# 23005_4.net
KiCad netlist of a schematic drawn in Altium Designer
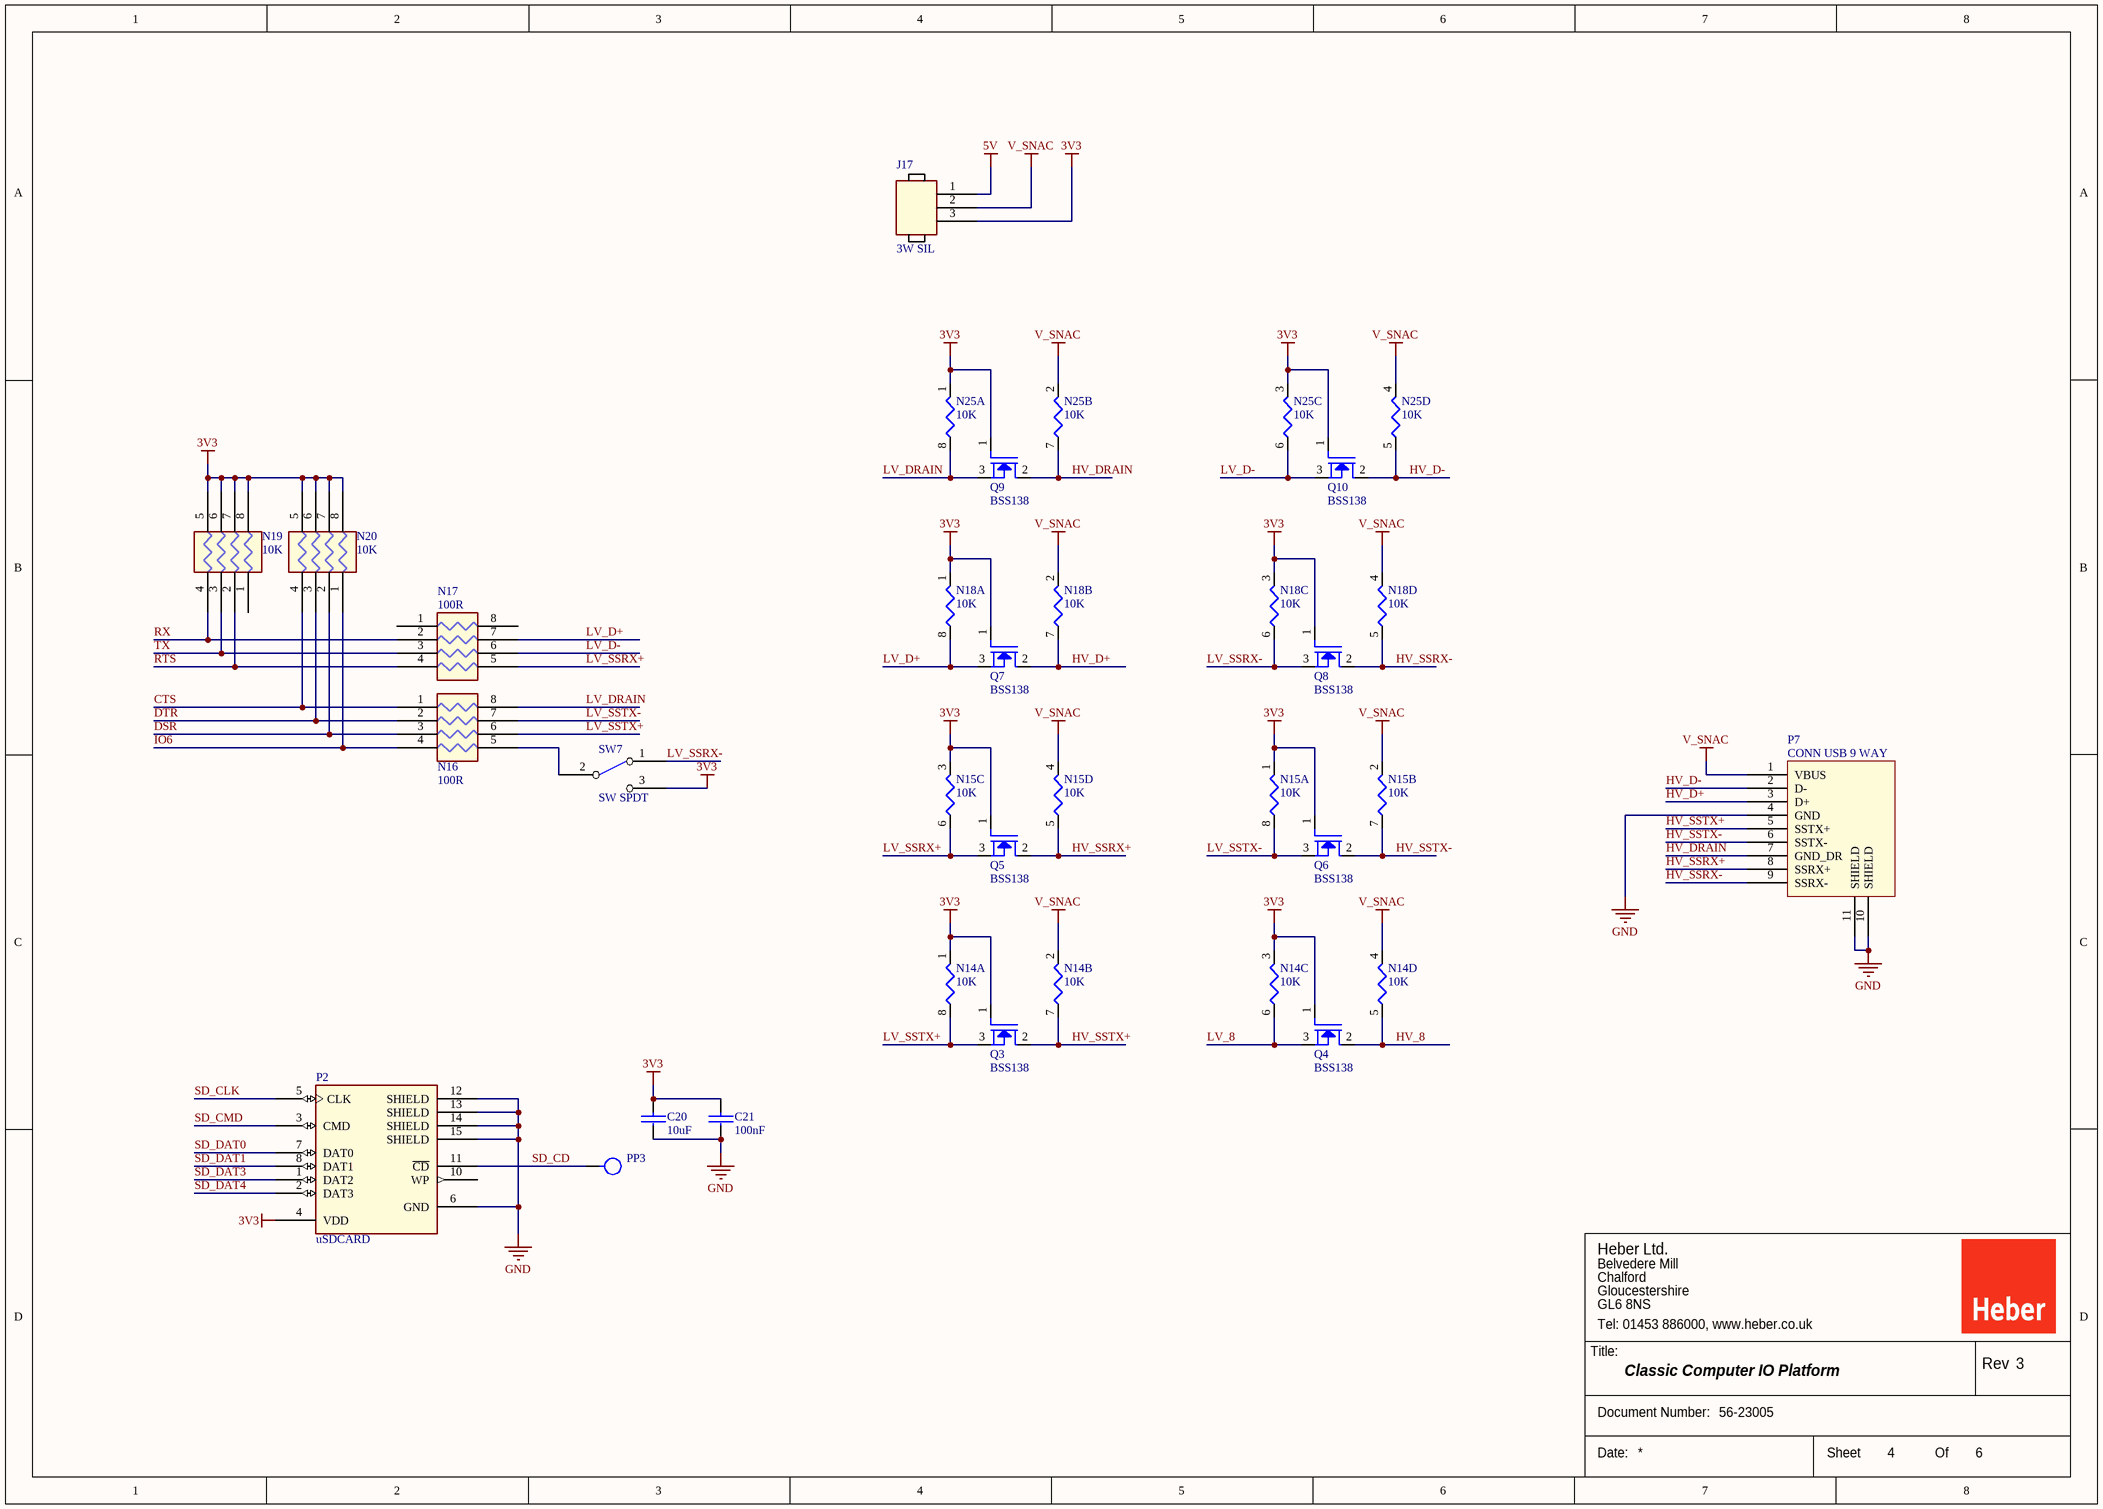
[diagram p0: 23005_4.SchDoc]

(export (version "E")
  (design (tool "Eeschema 10.0.6"))
  (components
    (comp (ref "C20") (value "10uF") (footprint "SM0805") (libsource (lib "LIBRARY1_Library") (part "C")))
    (comp (ref "C21") (value "100nF") (footprint "SM0603") (libsource (lib "LIBRARY1_Library") (part "C")))
    (comp (ref "J17")
      (value "3W SIL")
      (footprint "3WSIL")
      (libsource (lib "LIBRARY1_Library") (part "HEADER 3"))
    )
    (comp (ref "N14")
      (value "10K")
      (footprint "1206RES4_I2")
      (libsource (lib "LIBRARY1_Library") (part "RESISTOR DIP 4 A-D"))
    )
    (comp (ref "N15")
      (value "10K")
      (footprint "1206RES4_I2")
      (libsource (lib "LIBRARY1_Library") (part "RESISTOR DIP 4 A-D"))
    )
    (comp (ref "N16")
      (value "100R")
      (footprint "1206RES4_I2")
      (libsource (lib "LIBRARY1_Library") (part "RESISTOR DIP 4"))
    )
    (comp (ref "N17")
      (value "100R")
      (footprint "1206RES4_I2")
      (libsource (lib "LIBRARY1_Library") (part "RESISTOR DIP 4"))
    )
    (comp (ref "N18")
      (value "10K")
      (footprint "1206RES4_I2")
      (libsource (lib "LIBRARY1_Library") (part "RESISTOR DIP 4 A-D"))
    )
    (comp (ref "N19")
      (value "10K")
      (footprint "1206RES4_I2")
      (libsource (lib "LIBRARY1_Library") (part "RESISTOR DIP 4"))
    )
    (comp (ref "N20")
      (value "10K")
      (footprint "1206RES4_I2")
      (libsource (lib "LIBRARY1_Library") (part "RESISTOR DIP 4"))
    )
    (comp (ref "N25")
      (value "10K")
      (footprint "1206RES4_I2")
      (libsource (lib "LIBRARY1_Library") (part "RESISTOR DIP 4 A-D"))
    )
    (comp (ref "P2")
      (value "uSDCARD")
      (footprint "AMP_114-00841-68")
      (libsource (lib "LIBRARY1_Library") (part "uSDCARD"))
    )
    (comp (ref "P7")
      (value "CONN USB 9 WAY")
      (footprint "WURTH_692121030100")
      (libsource (lib "23005") (part "CONN USB 9 WAY"))
    )
    (comp (ref "PP3")
      (value "PROBEPOINT_SHORT")
      (footprint "PROBEPOINT")
      (libsource (lib "LIBRARY1_Library") (part "PROBEPOINT_SHORT"))
    )
    (comp (ref "Q3")
      (value "BSS138")
      (footprint "SOT23")
      (libsource (lib "LIBRARY1_Library") (part "MOSFET N_0"))
    )
    (comp (ref "Q4")
      (value "BSS138")
      (footprint "SOT23")
      (libsource (lib "LIBRARY1_Library") (part "MOSFET N_0"))
    )
    (comp (ref "Q5")
      (value "BSS138")
      (footprint "SOT23")
      (libsource (lib "LIBRARY1_Library") (part "MOSFET N_0"))
    )
    (comp (ref "Q6")
      (value "BSS138")
      (footprint "SOT23")
      (libsource (lib "LIBRARY1_Library") (part "MOSFET N_0"))
    )
    (comp (ref "Q7")
      (value "BSS138")
      (footprint "SOT23")
      (libsource (lib "LIBRARY1_Library") (part "MOSFET N_0"))
    )
    (comp (ref "Q8")
      (value "BSS138")
      (footprint "SOT23")
      (libsource (lib "LIBRARY1_Library") (part "MOSFET N_0"))
    )
    (comp (ref "Q9")
      (value "BSS138")
      (footprint "SOT23")
      (libsource (lib "LIBRARY1_Library") (part "MOSFET N_0"))
    )
    (comp (ref "Q10")
      (value "BSS138")
      (footprint "SOT23")
      (libsource (lib "LIBRARY1_Library") (part "MOSFET N_0"))
    )
    (comp (ref "SW7")
      (value "SW SPDT")
      (footprint "SW_ITT_OS102011MS2QN1")
      (libsource (lib "LIBRARY1_Library") (part "SW SPDT"))
    )
  )
  (nets
    (net (code "1") (name "/CTS") (class "Default")
      (node (ref "N16") (pin "1") (pinfunction "1_1") (pintype "passive"))
      (node (ref "N20") (pin "4") (pinfunction "4_4") (pintype "passive"))
    )
    (net (code "2") (name "/DSR") (class "Default")
      (node (ref "N16") (pin "3") (pinfunction "3_3") (pintype "passive"))
      (node (ref "N20") (pin "2") (pinfunction "2_2") (pintype "passive"))
    )
    (net (code "3") (name "/DTR") (class "Default")
      (node (ref "N16") (pin "2") (pinfunction "2_2") (pintype "passive"))
      (node (ref "N20") (pin "3") (pinfunction "3_3") (pintype "passive"))
    )
    (net (code "4") (name "/HV_8") (class "Default")
      (node (ref "N14") (pin "5") (pinfunction "2_5") (pintype "passive"))
      (node (ref "Q4") (pin "2") (pinfunction "DRAIN_2") (pintype "passive"))
    )
    (net (code "5") (name "/HV_D+") (class "Default")
      (node (ref "N18") (pin "7") (pinfunction "2_7") (pintype "passive"))
      (node (ref "P7") (pin "3") (pinfunction "D+_3") (pintype "passive"))
      (node (ref "Q7") (pin "2") (pinfunction "DRAIN_2") (pintype "passive"))
    )
    (net (code "6") (name "/HV_D-") (class "Default")
      (node (ref "N25") (pin "5") (pinfunction "2_5") (pintype "passive"))
      (node (ref "P7") (pin "2") (pinfunction "D-_2") (pintype "passive"))
      (node (ref "Q10") (pin "2") (pinfunction "DRAIN_2") (pintype "passive"))
    )
    (net (code "7") (name "/HV_DRAIN") (class "Default")
      (node (ref "N25") (pin "7") (pinfunction "2_7") (pintype "passive"))
      (node (ref "P7") (pin "7") (pinfunction "GND_DR_7") (pintype "passive"))
      (node (ref "Q9") (pin "2") (pinfunction "DRAIN_2") (pintype "passive"))
    )
    (net (code "8") (name "/HV_SSRX+") (class "Default")
      (node (ref "N15") (pin "5") (pinfunction "2_5") (pintype "passive"))
      (node (ref "P7") (pin "8") (pinfunction "SSRX+_8") (pintype "passive"))
      (node (ref "Q5") (pin "2") (pinfunction "DRAIN_2") (pintype "passive"))
    )
    (net (code "9") (name "/HV_SSRX-") (class "Default")
      (node (ref "N18") (pin "5") (pinfunction "2_5") (pintype "passive"))
      (node (ref "P7") (pin "9") (pinfunction "SSRX-_9") (pintype "passive"))
      (node (ref "Q8") (pin "2") (pinfunction "DRAIN_2") (pintype "passive"))
    )
    (net (code "10") (name "/HV_SSTX+") (class "Default")
      (node (ref "N14") (pin "7") (pinfunction "2_7") (pintype "passive"))
      (node (ref "P7") (pin "5") (pinfunction "SSTX+_5") (pintype "passive"))
      (node (ref "Q3") (pin "2") (pinfunction "DRAIN_2") (pintype "passive"))
    )
    (net (code "11") (name "/HV_SSTX-") (class "Default")
      (node (ref "N15") (pin "7") (pinfunction "2_7") (pintype "passive"))
      (node (ref "P7") (pin "6") (pinfunction "SSTX-_6") (pintype "passive"))
      (node (ref "Q6") (pin "2") (pinfunction "DRAIN_2") (pintype "passive"))
    )
    (net (code "12") (name "/IO6") (class "Default")
      (node (ref "N16") (pin "4") (pinfunction "4_4") (pintype "passive"))
      (node (ref "N20") (pin "1") (pinfunction "1_1") (pintype "passive"))
    )
    (net (code "13") (name "/LV_8") (class "Default")
      (node (ref "N14") (pin "6") (pinfunction "2_6") (pintype "passive"))
      (node (ref "Q4") (pin "3") (pinfunction "SOURCE_3") (pintype "passive"))
    )
    (net (code "14") (name "/LV_D+") (class "Default")
      (node (ref "N17") (pin "7") (pinfunction "7_7") (pintype "passive"))
      (node (ref "N18") (pin "8") (pinfunction "2_8") (pintype "passive"))
      (node (ref "Q7") (pin "3") (pinfunction "SOURCE_3") (pintype "passive"))
    )
    (net (code "15") (name "/LV_D-") (class "Default")
      (node (ref "N17") (pin "6") (pinfunction "6_6") (pintype "passive"))
      (node (ref "N25") (pin "6") (pinfunction "2_6") (pintype "passive"))
      (node (ref "Q10") (pin "3") (pinfunction "SOURCE_3") (pintype "passive"))
    )
    (net (code "16") (name "/LV_DRAIN") (class "Default")
      (node (ref "N16") (pin "8") (pinfunction "8_8") (pintype "passive"))
      (node (ref "N25") (pin "8") (pinfunction "2_8") (pintype "passive"))
      (node (ref "Q9") (pin "3") (pinfunction "SOURCE_3") (pintype "passive"))
    )
    (net (code "17") (name "/LV_SSRX+") (class "Default")
      (node (ref "N15") (pin "6") (pinfunction "2_6") (pintype "passive"))
      (node (ref "N17") (pin "5") (pinfunction "5_5") (pintype "passive"))
      (node (ref "Q5") (pin "3") (pinfunction "SOURCE_3") (pintype "passive"))
    )
    (net (code "18") (name "/LV_SSRX-") (class "Default")
      (node (ref "N18") (pin "6") (pinfunction "2_6") (pintype "passive"))
      (node (ref "Q8") (pin "3") (pinfunction "SOURCE_3") (pintype "passive"))
      (node (ref "SW7") (pin "1") (pinfunction "NC_1") (pintype "passive"))
    )
    (net (code "19") (name "/LV_SSTX+") (class "Default")
      (node (ref "N14") (pin "8") (pinfunction "2_8") (pintype "passive"))
      (node (ref "N16") (pin "6") (pinfunction "6_6") (pintype "passive"))
      (node (ref "Q3") (pin "3") (pinfunction "SOURCE_3") (pintype "passive"))
    )
    (net (code "20") (name "/LV_SSTX-") (class "Default")
      (node (ref "N15") (pin "8") (pinfunction "2_8") (pintype "passive"))
      (node (ref "N16") (pin "7") (pinfunction "7_7") (pintype "passive"))
      (node (ref "Q6") (pin "3") (pinfunction "SOURCE_3") (pintype "passive"))
    )
    (net (code "21") (name "/RTS") (class "Default")
      (node (ref "N17") (pin "4") (pinfunction "4_4") (pintype "passive"))
      (node (ref "N19") (pin "2") (pinfunction "2_2") (pintype "passive"))
    )
    (net (code "22") (name "/RX") (class "Default")
      (node (ref "N17") (pin "2") (pinfunction "2_2") (pintype "passive"))
      (node (ref "N19") (pin "4") (pinfunction "4_4") (pintype "passive"))
    )
    (net (code "23") (name "/SD_CD") (class "Default")
      (node (ref "P2") (pin "11") (pinfunction "~{CD}_11") (pintype "passive"))
      (node (ref "PP3") (pin "1") (pinfunction "1_1") (pintype "passive"))
    )
    (net (code "24") (name "/SD_CLK") (class "Default")
      (node (ref "P2") (pin "5") (pinfunction "CLK_5") (pintype "bidirectional"))
    )
    (net (code "25") (name "/SD_CMD") (class "Default")
      (node (ref "P2") (pin "3") (pinfunction "CMD_3") (pintype "bidirectional"))
    )
    (net (code "26") (name "/SD_DAT0") (class "Default")
      (node (ref "P2") (pin "7") (pinfunction "DAT0_7") (pintype "bidirectional"))
    )
    (net (code "27") (name "/SD_DAT1") (class "Default")
      (node (ref "P2") (pin "8") (pinfunction "DAT1_8") (pintype "bidirectional"))
    )
    (net (code "28") (name "/SD_DAT3") (class "Default")
      (node (ref "P2") (pin "1") (pinfunction "DAT2_1") (pintype "bidirectional"))
    )
    (net (code "29") (name "/SD_DAT4") (class "Default")
      (node (ref "P2") (pin "2") (pinfunction "DAT3_2") (pintype "bidirectional"))
    )
    (net (code "30") (name "/TX") (class "Default")
      (node (ref "N17") (pin "3") (pinfunction "3_3") (pintype "passive"))
      (node (ref "N19") (pin "3") (pinfunction "3_3") (pintype "passive"))
    )
    (net (code "31") (name "3V3") (class "Default")
      (node (ref "C20") (pin "1") (pinfunction "1_1") (pintype "passive"))
      (node (ref "C21") (pin "1") (pinfunction "1_1") (pintype "passive"))
      (node (ref "J17") (pin "3") (pinfunction "3_3") (pintype "passive"))
      (node (ref "N14") (pin "1") (pinfunction "1_1") (pintype "passive"))
      (node (ref "N14") (pin "3") (pinfunction "1_3") (pintype "passive"))
      (node (ref "N15") (pin "1") (pinfunction "1_1") (pintype "passive"))
      (node (ref "N15") (pin "3") (pinfunction "1_3") (pintype "passive"))
      (node (ref "N18") (pin "1") (pinfunction "1_1") (pintype "passive"))
      (node (ref "N18") (pin "3") (pinfunction "1_3") (pintype "passive"))
      (node (ref "N19") (pin "5") (pinfunction "5_5") (pintype "passive"))
      (node (ref "N19") (pin "6") (pinfunction "6_6") (pintype "passive"))
      (node (ref "N19") (pin "7") (pinfunction "7_7") (pintype "passive"))
      (node (ref "N19") (pin "8") (pinfunction "8_8") (pintype "passive"))
      (node (ref "N20") (pin "5") (pinfunction "5_5") (pintype "passive"))
      (node (ref "N20") (pin "6") (pinfunction "6_6") (pintype "passive"))
      (node (ref "N20") (pin "7") (pinfunction "7_7") (pintype "passive"))
      (node (ref "N20") (pin "8") (pinfunction "8_8") (pintype "passive"))
      (node (ref "N25") (pin "1") (pinfunction "1_1") (pintype "passive"))
      (node (ref "N25") (pin "3") (pinfunction "1_3") (pintype "passive"))
      (node (ref "P2") (pin "4") (pinfunction "VDD_4") (pintype "power_in"))
      (node (ref "Q10") (pin "1") (pinfunction "GATE_1") (pintype "passive"))
      (node (ref "Q3") (pin "1") (pinfunction "GATE_1") (pintype "passive"))
      (node (ref "Q4") (pin "1") (pinfunction "GATE_1") (pintype "passive"))
      (node (ref "Q5") (pin "1") (pinfunction "GATE_1") (pintype "passive"))
      (node (ref "Q6") (pin "1") (pinfunction "GATE_1") (pintype "passive"))
      (node (ref "Q7") (pin "1") (pinfunction "GATE_1") (pintype "passive"))
      (node (ref "Q8") (pin "1") (pinfunction "GATE_1") (pintype "passive"))
      (node (ref "Q9") (pin "1") (pinfunction "GATE_1") (pintype "passive"))
      (node (ref "SW7") (pin "3") (pinfunction "NO_3") (pintype "passive"))
    )
    (net (code "32") (name "5V") (class "Default")
      (node (ref "J17") (pin "1") (pinfunction "1_1") (pintype "passive"))
    )
    (net (code "33") (name "GND") (class "Default")
      (node (ref "C20") (pin "2") (pinfunction "2_2") (pintype "passive"))
      (node (ref "C21") (pin "2") (pinfunction "2_2") (pintype "passive"))
      (node (ref "P2") (pin "12") (pinfunction "SHIELD_12") (pintype "power_in"))
      (node (ref "P2") (pin "13") (pinfunction "SHIELD_13") (pintype "power_in"))
      (node (ref "P2") (pin "14") (pinfunction "SHIELD_14") (pintype "power_in"))
      (node (ref "P2") (pin "15") (pinfunction "SHIELD_15") (pintype "power_in"))
      (node (ref "P2") (pin "6") (pinfunction "GND_6") (pintype "power_in"))
      (node (ref "P7") (pin "10") (pinfunction "SHIELD_10") (pintype "passive"))
      (node (ref "P7") (pin "11") (pinfunction "SHIELD_11") (pintype "passive"))
      (node (ref "P7") (pin "4") (pinfunction "GND_4") (pintype "passive"))
    )
    (net (code "34") (name "Net-(SW7-COMMON)") (class "Default")
      (node (ref "N16") (pin "5") (pinfunction "5_5") (pintype "passive"))
      (node (ref "SW7") (pin "2") (pinfunction "COMMON_2") (pintype "passive"))
    )
    (net (code "35") (name "V_SNAC") (class "Default")
      (node (ref "J17") (pin "2") (pinfunction "2_2") (pintype "passive"))
      (node (ref "N14") (pin "2") (pinfunction "1_2") (pintype "passive"))
      (node (ref "N14") (pin "4") (pinfunction "1_4") (pintype "passive"))
      (node (ref "N15") (pin "2") (pinfunction "1_2") (pintype "passive"))
      (node (ref "N15") (pin "4") (pinfunction "1_4") (pintype "passive"))
      (node (ref "N18") (pin "2") (pinfunction "1_2") (pintype "passive"))
      (node (ref "N18") (pin "4") (pinfunction "1_4") (pintype "passive"))
      (node (ref "N25") (pin "2") (pinfunction "1_2") (pintype "passive"))
      (node (ref "N25") (pin "4") (pinfunction "1_4") (pintype "passive"))
      (node (ref "P7") (pin "1") (pinfunction "VBUS_1") (pintype "passive"))
    )
    (net (code "36") (name "unconnected-(N17-Pad1)") (class "Default")
      (node (ref "N17") (pin "1") (pinfunction "1_1") (pintype "passive"))
    )
    (net (code "37") (name "unconnected-(N17-Pad8)") (class "Default")
      (node (ref "N17") (pin "8") (pinfunction "8_8") (pintype "passive"))
    )
    (net (code "38") (name "unconnected-(N19-Pad1)") (class "Default")
      (node (ref "N19") (pin "1") (pinfunction "1_1") (pintype "passive"))
    )
    (net (code "39") (name "unconnected-(P2-WP-Pad10)") (class "Default")
      (node (ref "P2") (pin "10") (pinfunction "WP_10") (pintype "output"))
    )
  )
)
